# USB_HUB.net
KiCad netlist of a schematic drawn in Altium Designer
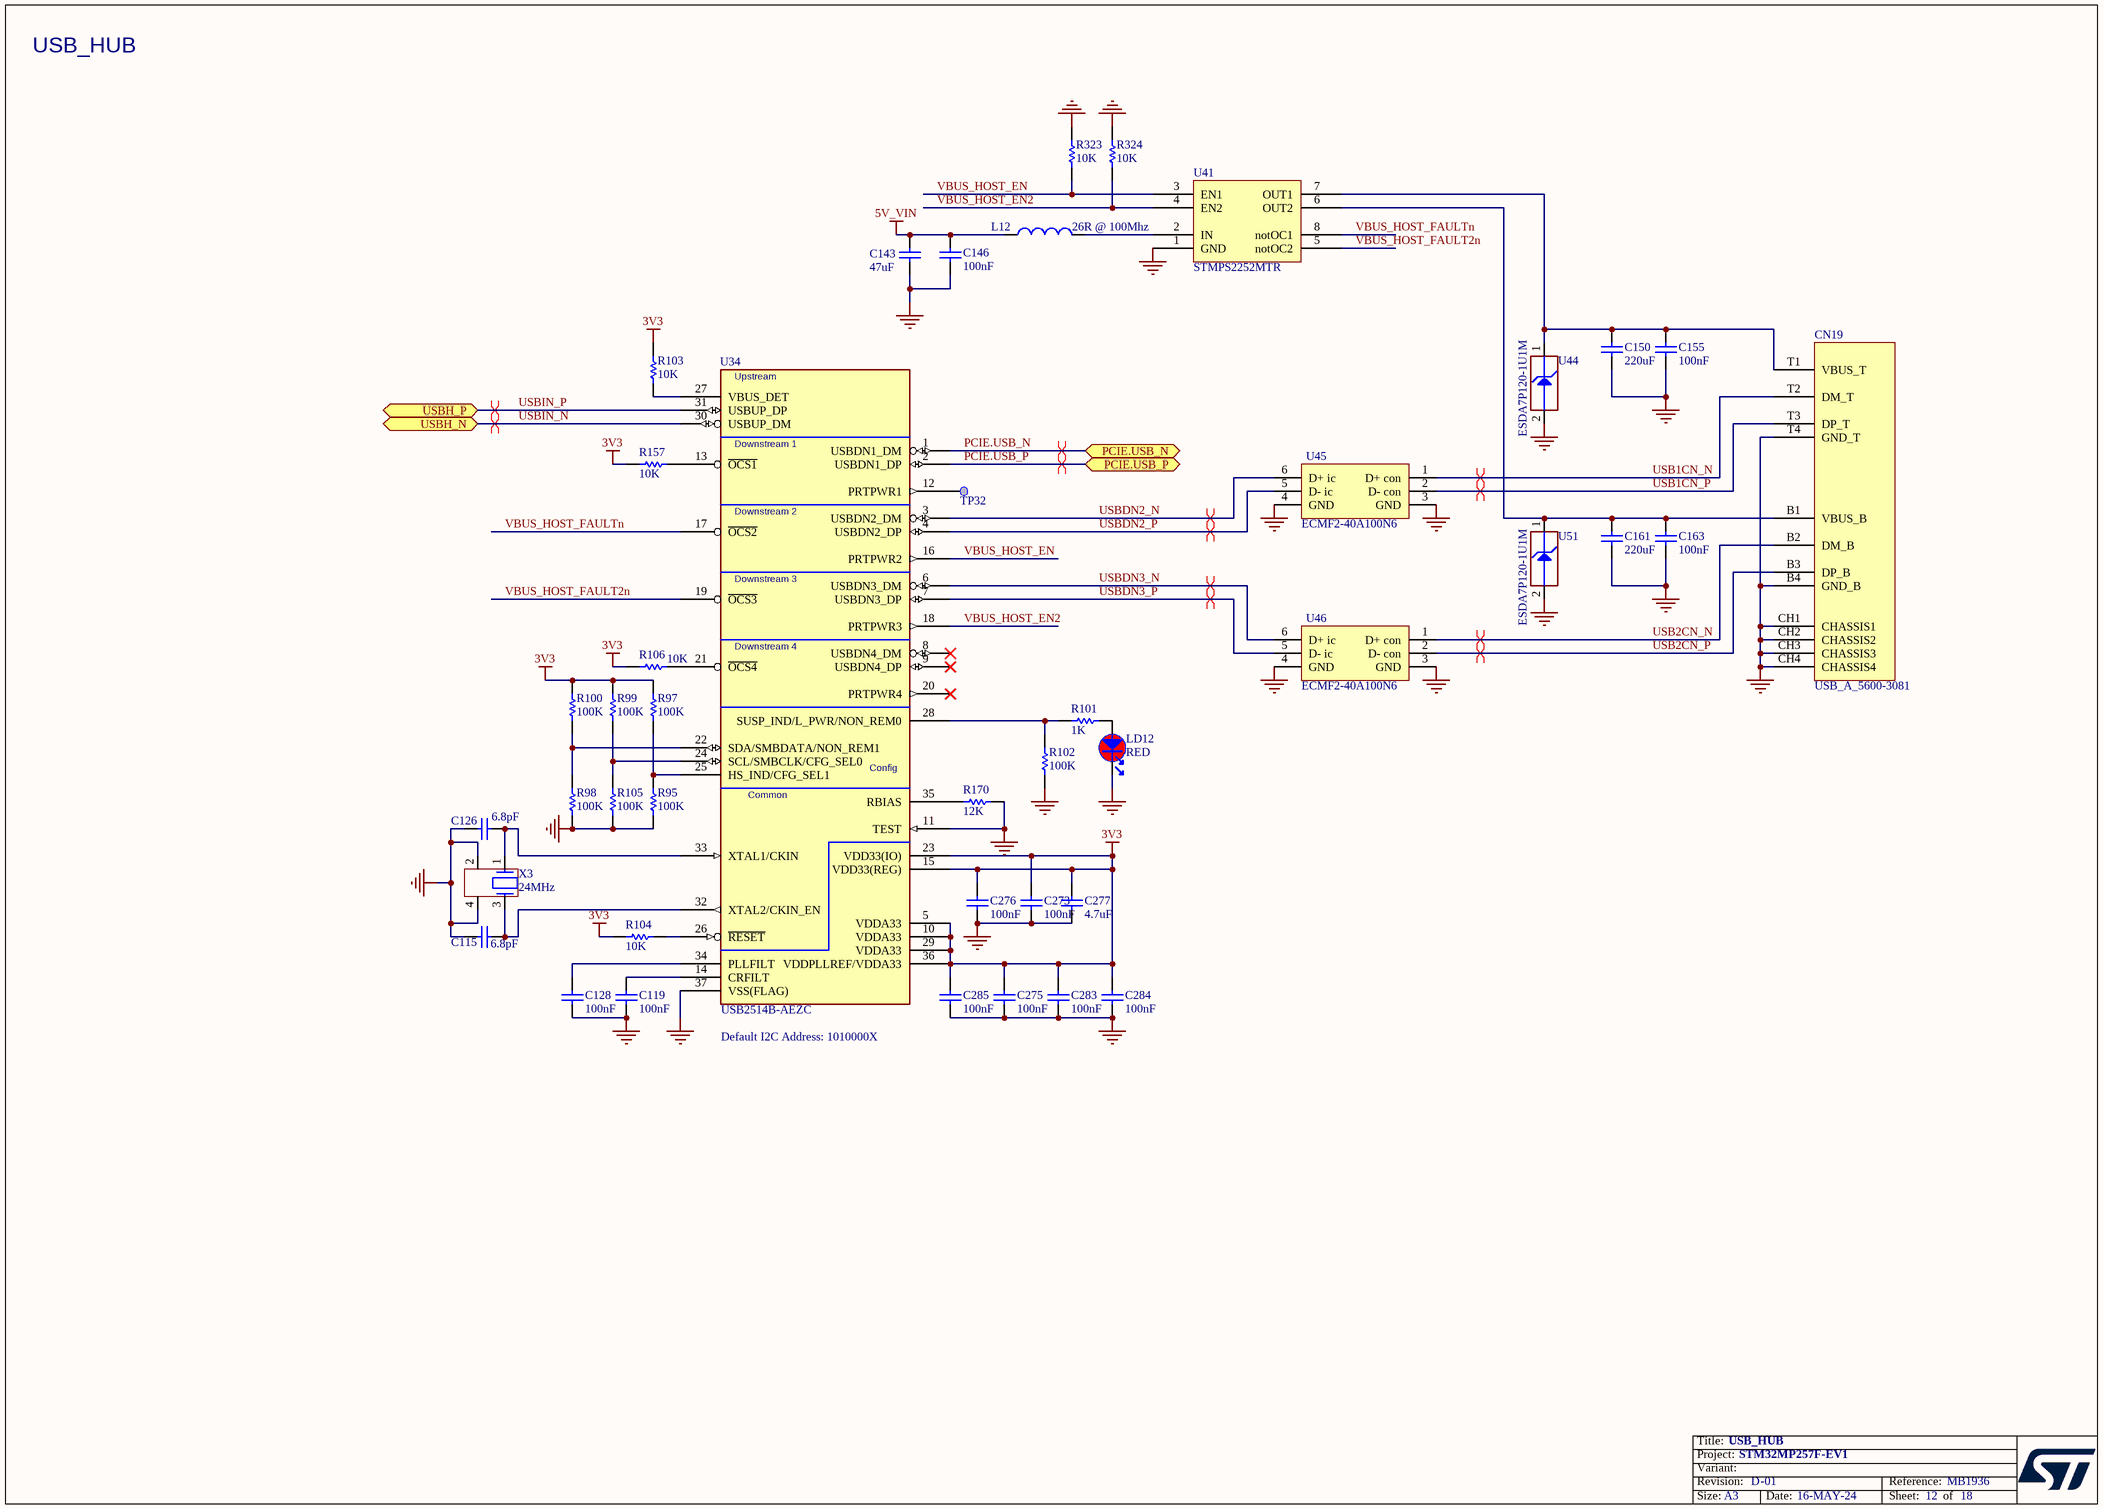
[diagram p0: USB_HUB.SchDoc]

(export (version "E")
  (design (tool "Eeschema 10.0.6"))
  (components
    (comp (ref "C115")
      (value "6.8pF")
      (footprint "MCD_PARTS:C0402")
      (description "Capacitor, MLCC, 6.8pF, 50V, NPO, +/-0.25pF, 0402, T=0.5mm")
      (fields
        (field (name "INTERNAL_PART_NUMBER") "MCD-00674")
        (field (name "MANUFACTURER_PART_NUMBER") "CC0402CRNPO9BN6R8")
      )
      (libsource (lib "MCD_PARTS_database") (part "Capacitor"))
    )
    (comp (ref "C119")
      (value "100nF")
      (footprint "MCD_PARTS:C0402")
      (description "Capacitor, MLCC, 100nF, 16V, X7R, +/-10%, 0402, T=0.5mm")
      (fields
        (field (name "INTERNAL_PART_NUMBER") "MCD-00006")
        (field (name "MANUFACTURER_PART_NUMBER") "CC0402KRX7R7BB104")
      )
      (libsource (lib "MCD_PARTS_database") (part "Capacitor"))
    )
    (comp (ref "C126")
      (value "6.8pF")
      (footprint "MCD_PARTS:C0402")
      (description "Capacitor, MLCC, 6.8pF, 50V, NPO, +/-0.25pF, 0402, T=0.5mm")
      (fields
        (field (name "INTERNAL_PART_NUMBER") "MCD-00674")
        (field (name "MANUFACTURER_PART_NUMBER") "CC0402CRNPO9BN6R8")
      )
      (libsource (lib "MCD_PARTS_database") (part "Capacitor"))
    )
    (comp (ref "C128")
      (value "100nF")
      (footprint "MCD_PARTS:C0402")
      (description "Capacitor, MLCC, 100nF, 16V, X7R, +/-10%, 0402, T=0.5mm")
      (fields
        (field (name "INTERNAL_PART_NUMBER") "MCD-00006")
        (field (name "MANUFACTURER_PART_NUMBER") "CC0402KRX7R7BB104")
      )
      (libsource (lib "MCD_PARTS_database") (part "Capacitor"))
    )
    (comp (ref "C143")
      (value "47uF")
      (footprint "MCD_PARTS:C0805")
      (description "Capacitor, MLCC, 47uF, 10V, X5R, +/-20%, 0805, T=1.25mm")
      (fields (field (name "INTERNAL_PART_NUMBER") "MCD-00204") (field (name "MANUFACTURER") "MURATA"))
      (libsource (lib "MCD_PARTS_database") (part "Capacitor"))
    )
    (comp (ref "C146")
      (value "100nF")
      (footprint "MCD_PARTS:C0402")
      (description "Capacitor, MLCC, 100nF, 16V, X7R, +/-10%, 0402, T=0.5mm")
      (fields
        (field (name "INTERNAL_PART_NUMBER") "MCD-00006")
        (field (name "MANUFACTURER_PART_NUMBER") "CC0402KRX7R7BB104")
      )
      (libsource (lib "MCD_PARTS_database") (part "Capacitor"))
    )
    (comp (ref "C150")
      (value "220uF")
      (footprint "MCD_PARTS:C1206_H1P6")
      (description "Capacitor, MLCC, 220uF, 6V3, X5R, +/-20%, 1206, T=1.6mm")
      (fields
        (field (name "INTERNAL_PART_NUMBER") "MCD-00104")
        (field (name "MANUFACTURER_PART_NUMBER") "GRM31CR60J227ME11")
      )
      (libsource (lib "MCD_PARTS_database") (part "Capacitor"))
    )
    (comp (ref "C155")
      (value "100nF")
      (footprint "MCD_PARTS:C0402")
      (description "Capacitor, MLCC, 100nF, 16V, X7R, +/-10%, 0402, T=0.5mm")
      (fields
        (field (name "INTERNAL_PART_NUMBER") "MCD-00006")
        (field (name "MANUFACTURER_PART_NUMBER") "CC0402KRX7R7BB104")
      )
      (libsource (lib "MCD_PARTS_database") (part "Capacitor"))
    )
    (comp (ref "C161")
      (value "220uF")
      (footprint "MCD_PARTS:C1206_H1P6")
      (description "Capacitor, MLCC, 220uF, 6V3, X5R, +/-20%, 1206, T=1.6mm")
      (fields
        (field (name "INTERNAL_PART_NUMBER") "MCD-00104")
        (field (name "MANUFACTURER_PART_NUMBER") "GRM31CR60J227ME11")
      )
      (libsource (lib "MCD_PARTS_database") (part "Capacitor"))
    )
    (comp (ref "C163")
      (value "100nF")
      (footprint "MCD_PARTS:C0402")
      (description "Capacitor, MLCC, 100nF, 16V, X7R, +/-10%, 0402, T=0.5mm")
      (fields
        (field (name "INTERNAL_PART_NUMBER") "MCD-00006")
        (field (name "MANUFACTURER_PART_NUMBER") "CC0402KRX7R7BB104")
      )
      (libsource (lib "MCD_PARTS_database") (part "Capacitor"))
    )
    (comp (ref "C273")
      (value "100nF")
      (footprint "MCD_PARTS:C0402")
      (description "Capacitor, MLCC, 100nF, 16V, X7R, +/-10%, 0402, T=0.5mm")
      (fields
        (field (name "INTERNAL_PART_NUMBER") "MCD-00006")
        (field (name "MANUFACTURER_PART_NUMBER") "CC0402KRX7R7BB104")
      )
      (libsource (lib "MCD_PARTS_database") (part "Capacitor"))
    )
    (comp (ref "C275")
      (value "100nF")
      (footprint "MCD_PARTS:C0402")
      (description "Capacitor, MLCC, 100nF, 16V, X7R, +/-10%, 0402, T=0.5mm")
      (fields
        (field (name "INTERNAL_PART_NUMBER") "MCD-00006")
        (field (name "MANUFACTURER_PART_NUMBER") "CC0402KRX7R7BB104")
      )
      (libsource (lib "MCD_PARTS_database") (part "Capacitor"))
    )
    (comp (ref "C276")
      (value "100nF")
      (footprint "MCD_PARTS:C0402")
      (description "Capacitor, MLCC, 100nF, 16V, X7R, +/-10%, 0402, T=0.5mm")
      (fields
        (field (name "INTERNAL_PART_NUMBER") "MCD-00006")
        (field (name "MANUFACTURER_PART_NUMBER") "CC0402KRX7R7BB104")
      )
      (libsource (lib "MCD_PARTS_database") (part "Capacitor"))
    )
    (comp (ref "C277")
      (value "4.7uF")
      (footprint "MCD_PARTS:C0402")
      (description "Capacitor, MLCC, 4.7uF, 6V3, X5R, +/-20%, 0402, T=0.5mm")
      (fields
        (field (name "INTERNAL_PART_NUMBER") "MCD-01356")
        (field (name "MANUFACTURER_PART_NUMBER") "GRM155R60J475ME47")
      )
      (libsource (lib "MCD_PARTS_database") (part "Capacitor"))
    )
    (comp (ref "C283")
      (value "100nF")
      (footprint "MCD_PARTS:C0402")
      (description "Capacitor, MLCC, 100nF, 16V, X7R, +/-10%, 0402, T=0.5mm")
      (fields
        (field (name "INTERNAL_PART_NUMBER") "MCD-00006")
        (field (name "MANUFACTURER_PART_NUMBER") "CC0402KRX7R7BB104")
      )
      (libsource (lib "MCD_PARTS_database") (part "Capacitor"))
    )
    (comp (ref "C284")
      (value "100nF")
      (footprint "MCD_PARTS:C0402")
      (description "Capacitor, MLCC, 100nF, 16V, X7R, +/-10%, 0402, T=0.5mm")
      (fields
        (field (name "INTERNAL_PART_NUMBER") "MCD-00006")
        (field (name "MANUFACTURER_PART_NUMBER") "CC0402KRX7R7BB104")
      )
      (libsource (lib "MCD_PARTS_database") (part "Capacitor"))
    )
    (comp (ref "C285")
      (value "100nF")
      (footprint "MCD_PARTS:C0402")
      (description "Capacitor, MLCC, 100nF, 16V, X7R, +/-10%, 0402, T=0.5mm")
      (fields
        (field (name "INTERNAL_PART_NUMBER") "MCD-00006")
        (field (name "MANUFACTURER_PART_NUMBER") "CC0402KRX7R7BB104")
      )
      (libsource (lib "MCD_PARTS_database") (part "Capacitor"))
    )
    (comp (ref "CN19")
      (value "USB_A_5600-3081")
      (footprint "MCD_PARTS:CON_DUAL-USB-TYPE-A_CONEXCON_5600-3081")
      (description "USB_Dual-TypeA, Receptacle, 8pins, 2.5mm, RA, TH, T= 15.5mm")
      (fields
        (field (name "INTERNAL_PART_NUMBER") "MCD-00109")
        (field (name "MANUFACTURER_PART_NUMBER") "5600-3081")
      )
      (libsource (lib "MCD_PARTS_database") (part "USB_DUAL_TYPEA_5600-3081"))
    )
    (comp (ref "L12")
      (value "26R @ 100Mhz")
      (footprint "MCD_PARTS:FIL_0603_H0P65")
      (description "Ferrite bead, 26R @ 100Mhz, +/-25%, 6000mA, 0R007, 0603, T=0.75mm")
      (fields
        (field (name "INTERNAL_PART_NUMBER") "MCD-00305")
        (field (name "MANUFACTURER_PART_NUMBER") "BLM18KG260TN1")
      )
      (libsource (lib "MCD_PARTS_database") (part "BEAD"))
    )
    (comp (ref "LD12")
      (value "RED")
      (footprint "MCD_PARTS:LED_0603_VISHAY_VLMS1300-GS08_RED_1A2K_H0P8")
      (description "LED Red, 0603 SMD, 2V Forward Voltage")
      (fields
        (field (name "INTERNAL_PART_NUMBER") "MCD-00587")
        (field (name "MANUFACTURER_PART_NUMBER") "VLMS1300-GS08")
        (field (name "PROVIDED_BY") "SUBCO")
      )
      (libsource (lib "MCD_PARTS_database") (part "LED_red"))
    )
    (comp (ref "R95")
      (value "100K")
      (footprint "MCD_PARTS:R0402")
      (description "Resistor, 100K, 0402, +/-1%, 1/16W")
      (fields
        (field (name "INTERNAL_PART_NUMBER") "MCD-00059")
        (field (name "MANUFACTURER_PART_NUMBER") "RC0402FR-07100KL")
      )
      (libsource (lib "MCD_PARTS_database") (part "Resistor"))
    )
    (comp (ref "R97")
      (value "100K")
      (footprint "MCD_PARTS:R0402")
      (description "Resistor, 100K, 0402, +/-1%, 1/16W")
      (fields
        (field (name "INTERNAL_PART_NUMBER") "MCD-00059")
        (field (name "MANUFACTURER_PART_NUMBER") "RC0402FR-07100KL")
      )
      (libsource (lib "MCD_PARTS_database") (part "Resistor"))
    )
    (comp (ref "R98")
      (value "100K")
      (footprint "MCD_PARTS:R0402")
      (description "Resistor, 100K, 0402, +/-1%, 1/16W")
      (fields
        (field (name "INTERNAL_PART_NUMBER") "MCD-00059")
        (field (name "MANUFACTURER_PART_NUMBER") "RC0402FR-07100KL")
      )
      (libsource (lib "MCD_PARTS_database") (part "Resistor"))
    )
    (comp (ref "R99")
      (value "100K")
      (footprint "MCD_PARTS:R0402")
      (description "Resistor, 100K, 0402, +/-1%, 1/16W")
      (fields
        (field (name "INTERNAL_PART_NUMBER") "MCD-00059")
        (field (name "MANUFACTURER_PART_NUMBER") "RC0402FR-07100KL")
      )
      (libsource (lib "MCD_PARTS_database") (part "Resistor"))
    )
    (comp (ref "R100")
      (value "100K")
      (footprint "MCD_PARTS:R0402")
      (description "Resistor, 100K, 0402, +/-1%, 1/16W")
      (fields
        (field (name "INTERNAL_PART_NUMBER") "MCD-00059")
        (field (name "MANUFACTURER_PART_NUMBER") "RC0402FR-07100KL")
      )
      (libsource (lib "MCD_PARTS_database") (part "Resistor"))
    )
    (comp (ref "R101")
      (value "1K")
      (footprint "MCD_PARTS:R0402")
      (description "Resistor, 1K, 0402, +/-1%,1/16W")
      (fields
        (field (name "INTERNAL_PART_NUMBER") "MCD-00061")
        (field (name "MANUFACTURER_PART_NUMBER") "RC0402FR-071KL")
      )
      (libsource (lib "MCD_PARTS_database") (part "Resistor"))
    )
    (comp (ref "R102")
      (value "100K")
      (footprint "MCD_PARTS:R0402")
      (description "Resistor, 100K, 0402, +/-1%, 1/16W")
      (fields
        (field (name "INTERNAL_PART_NUMBER") "MCD-00059")
        (field (name "MANUFACTURER_PART_NUMBER") "RC0402FR-07100KL")
      )
      (libsource (lib "MCD_PARTS_database") (part "Resistor"))
    )
    (comp (ref "R103")
      (value "10K")
      (footprint "MCD_PARTS:R0402")
      (description "Resistor, 10K, 0402, +/-1%, 1/16W")
      (fields
        (field (name "INTERNAL_PART_NUMBER") "MCD-00053")
        (field (name "MANUFACTURER_PART_NUMBER") "RC0402FR-0710KL")
      )
      (libsource (lib "MCD_PARTS_database") (part "Resistor"))
    )
    (comp (ref "R104")
      (value "10K")
      (footprint "MCD_PARTS:R0402")
      (description "Resistor, 10K, 0402, +/-1%, 1/16W")
      (fields
        (field (name "INTERNAL_PART_NUMBER") "MCD-00053")
        (field (name "MANUFACTURER_PART_NUMBER") "RC0402FR-0710KL")
      )
      (libsource (lib "MCD_PARTS_database") (part "Resistor"))
    )
    (comp (ref "R105")
      (value "100K")
      (footprint "MCD_PARTS:R0402")
      (description "Resistor, 100K, 0402, +/-1%, 1/16W")
      (fields
        (field (name "INTERNAL_PART_NUMBER") "MCD-00059")
        (field (name "MANUFACTURER_PART_NUMBER") "RC0402FR-07100KL")
      )
      (libsource (lib "MCD_PARTS_database") (part "Resistor"))
    )
    (comp (ref "R106")
      (value "10K")
      (footprint "MCD_PARTS:R0402")
      (description "Resistor, 10K, 0402, +/-1%, 1/16W")
      (fields
        (field (name "INTERNAL_PART_NUMBER") "MCD-00053")
        (field (name "MANUFACTURER_PART_NUMBER") "RC0402FR-0710KL")
      )
      (libsource (lib "MCD_PARTS_database") (part "Resistor"))
    )
    (comp (ref "R157")
      (value "10K")
      (footprint "MCD_PARTS:R0402")
      (description "Resistor, 10K, 0402, +/-1%, 1/16W")
      (fields
        (field (name "INTERNAL_PART_NUMBER") "MCD-00053")
        (field (name "MANUFACTURER_PART_NUMBER") "RC0402FR-0710KL")
      )
      (libsource (lib "MCD_PARTS_database") (part "Resistor"))
    )
    (comp (ref "R170")
      (value "12K")
      (footprint "MCD_PARTS:R0402")
      (description "Resistor, 12K, 0402, +/-1%, 1/16W")
      (fields
        (field (name "INTERNAL_PART_NUMBER") "MCD-00187")
        (field (name "MANUFACTURER_PART_NUMBER") "RC0402FR-0712KL")
      )
      (libsource (lib "MCD_PARTS_database") (part "Resistor"))
    )
    (comp (ref "R323")
      (value "10K")
      (footprint "MCD_PARTS:R0402")
      (description "Resistor, 10K, 0402, +/-1%, 1/16W")
      (fields
        (field (name "INTERNAL_PART_NUMBER") "MCD-00053")
        (field (name "MANUFACTURER_PART_NUMBER") "RC0402FR-0710KL")
      )
      (libsource (lib "MCD_PARTS_database") (part "Resistor"))
    )
    (comp (ref "R324")
      (value "10K")
      (footprint "MCD_PARTS:R0402")
      (description "Resistor, 10K, 0402, +/-1%, 1/16W")
      (fields
        (field (name "INTERNAL_PART_NUMBER") "MCD-00053")
        (field (name "MANUFACTURER_PART_NUMBER") "RC0402FR-0710KL")
      )
      (libsource (lib "MCD_PARTS_database") (part "Resistor"))
    )
    (comp (ref "TP32")
      (value "Test Point")
      (footprint "MCD_PARTS:TP_SMD_1MM")
      (description "Test Point 1mm")
      (fields
        (field (name "INTERNAL_PART_NUMBER") "MCD-00074")
        (field (name "MANUFACTURER_PART_NUMBER") "n/a")
      )
      (libsource (lib "MCD_PARTS_database") (part "Test Point"))
    )
    (comp (ref "U34")
      (value "USB2514B-AEZC")
      (footprint "MCD_PARTS:ICC_QFN36-EPAD_6X6_P050")
      (description "USB HUB 2,0 Controller")
      (fields (field (name "INTERNAL_PART_NUMBER") "MCD-00145") (field (name "MANUFACTURER") "MICROCHIP"))
      (libsource (lib "MCD_PARTS_database") (part "USB2514B-AEZC"))
    )
    (comp (ref "U41")
      (value "STMPS2252MTR")
      (footprint "MCD_PARTS:ICC_SO8_5X4_P127")
      (description "IC,Dual-Channel-Power-Switch,500mA,100mR,SO8")
      (fields
        (field (name "INTERNAL_PART_NUMBER") "MCD-00123")
        (field (name "MANUFACTURER") "STMICROELECTRONICS")
      )
      (libsource (lib "MCD_PARTS_database") (part "STMPS2252MTR"))
    )
    (comp (ref "U44")
      (value "ESDA7P120-1U1M")
      (footprint "MCD_PARTS:ESD_QFN1610_2N_1K_2A")
      (description "High power transient voltage suppressor")
      (fields
        (field (name "INTERNAL_PART_NUMBER") "MCD-01026")
        (field (name "MANUFACTURER") "STMICROELECTRONICS")
      )
      (libsource (lib "MCD_PARTS_database") (part "ESD-TRANSIL"))
    )
    (comp (ref "U45")
      (value "ECMF2-40A100N6")
      (footprint "MCD_PARTS:ESD_UQFN-6L_1P45X1P4_P040")
      (description "ESD protection & Common Filter High Speed serial Interfaces , 0.4 pitch")
      (fields
        (field (name "INTERNAL_PART_NUMBER") "MCD-03060")
        (field (name "MANUFACTURER") "STMICROELECTRONICS")
      )
      (libsource (lib "MCD_PARTS_database") (part "ECMF2-40A100N6"))
    )
    (comp (ref "U46")
      (value "ECMF2-40A100N6")
      (footprint "MCD_PARTS:ESD_UQFN-6L_1P45X1P4_P040")
      (description "ESD protection & Common Filter High Speed serial Interfaces , 0.4 pitch")
      (fields
        (field (name "INTERNAL_PART_NUMBER") "MCD-03060")
        (field (name "MANUFACTURER") "STMICROELECTRONICS")
      )
      (libsource (lib "MCD_PARTS_database") (part "ECMF2-40A100N6"))
    )
    (comp (ref "U51")
      (value "ESDA7P120-1U1M")
      (footprint "MCD_PARTS:ESD_QFN1610_2N_1K_2A")
      (description "High power transient voltage suppressor")
      (fields
        (field (name "INTERNAL_PART_NUMBER") "MCD-01026")
        (field (name "MANUFACTURER") "STMICROELECTRONICS")
      )
      (libsource (lib "MCD_PARTS_database") (part "ESD-TRANSIL"))
    )
    (comp (ref "X3")
      (value "24MHz")
      (footprint "MCD_PARTS:CRY_NX2016SA_4P")
      (description "Crystal, 24MHz, 6pF, +/-20ppm, 80R, 2x1.6mm")
      (fields
        (field (name "INTERNAL_PART_NUMBER") "MCD-01036")
        (field (name "MANUFACTURER_PART_NUMBER") "NX2016SA-24MHZ-EXS00A-CS10820")
      )
      (libsource (lib "MCD_PARTS_database") (part "XTAL_4_PINS"))
    )
  )
  (nets
    (net (code "1") (name "/PCIE.USB_N") (class "Default")
      (node (ref "U34") (pin "1") (pinfunction "USBDN1_DM_1") (pintype "bidirectional"))
    )
    (net (code "2") (name "/PCIE.USB_P") (class "Default")
      (node (ref "U34") (pin "2") (pinfunction "USBDN1_DP_2") (pintype "bidirectional"))
    )
    (net (code "3") (name "/USB1CN_N") (class "Default")
      (node (ref "CN19") (pin "T2") (pinfunction "DM_T_T2") (pintype "passive"))
      (node (ref "U45") (pin "1") (pinfunction "D+_con_1") (pintype "passive"))
    )
    (net (code "4") (name "/USB1CN_P") (class "Default")
      (node (ref "CN19") (pin "T3") (pinfunction "DP_T_T3") (pintype "passive"))
      (node (ref "U45") (pin "2") (pinfunction "D-_con_2") (pintype "passive"))
    )
    (net (code "5") (name "/USB2CN_N") (class "Default")
      (node (ref "CN19") (pin "B2") (pinfunction "DM_B_B2") (pintype "passive"))
      (node (ref "U46") (pin "1") (pinfunction "D+_con_1") (pintype "passive"))
    )
    (net (code "6") (name "/USB2CN_P") (class "Default")
      (node (ref "CN19") (pin "B3") (pinfunction "DP_B_B3") (pintype "passive"))
      (node (ref "U46") (pin "2") (pinfunction "D-_con_2") (pintype "passive"))
    )
    (net (code "7") (name "/USBDN2_N") (class "Default")
      (node (ref "U34") (pin "3") (pinfunction "USBDN2_DM_3") (pintype "bidirectional"))
      (node (ref "U45") (pin "6") (pinfunction "D+_ic_6") (pintype "passive"))
    )
    (net (code "8") (name "/USBDN2_P") (class "Default")
      (node (ref "U34") (pin "4") (pinfunction "USBDN2_DP_4") (pintype "bidirectional"))
      (node (ref "U45") (pin "5") (pinfunction "D-_ic_5") (pintype "passive"))
    )
    (net (code "9") (name "/USBDN3_N") (class "Default")
      (node (ref "U34") (pin "6") (pinfunction "USBDN3_DM_6") (pintype "bidirectional"))
      (node (ref "U46") (pin "6") (pinfunction "D+_ic_6") (pintype "passive"))
    )
    (net (code "10") (name "/USBDN3_P") (class "Default")
      (node (ref "U34") (pin "7") (pinfunction "USBDN3_DP_7") (pintype "bidirectional"))
      (node (ref "U46") (pin "5") (pinfunction "D-_ic_5") (pintype "passive"))
    )
    (net (code "11") (name "/USBIN_N") (class "Default")
      (node (ref "U34") (pin "30") (pinfunction "USBUP_DM_30") (pintype "bidirectional"))
    )
    (net (code "12") (name "/USBIN_P") (class "Default")
      (node (ref "U34") (pin "31") (pinfunction "USBUP_DP_31") (pintype "bidirectional"))
    )
    (net (code "13") (name "/VBUS_HOST_EN") (class "Default")
      (node (ref "R323") (pin "2") (pinfunction "2_2") (pintype "passive"))
      (node (ref "U34") (pin "16") (pinfunction "PRTPWR2_16") (pintype "output"))
      (node (ref "U41") (pin "3") (pinfunction "EN1_3") (pintype "passive"))
    )
    (net (code "14") (name "/VBUS_HOST_EN2") (class "Default")
      (node (ref "R324") (pin "2") (pinfunction "2_2") (pintype "passive"))
      (node (ref "U34") (pin "18") (pinfunction "PRTPWR3_18") (pintype "output"))
      (node (ref "U41") (pin "4") (pinfunction "EN2_4") (pintype "passive"))
    )
    (net (code "15") (name "/VBUS_HOST_FAULT2n") (class "Default")
      (node (ref "U34") (pin "19") (pinfunction "~{OCS3}_19") (pintype "passive"))
      (node (ref "U41") (pin "5") (pinfunction "notOC2_5") (pintype "passive"))
    )
    (net (code "16") (name "/VBUS_HOST_FAULTn") (class "Default")
      (node (ref "U34") (pin "17") (pinfunction "~{OCS2}_17") (pintype "passive"))
      (node (ref "U41") (pin "8") (pinfunction "notOC1_8") (pintype "passive"))
    )
    (net (code "17") (name "3V3") (class "Default")
      (node (ref "C273") (pin "2") (pinfunction "2_2") (pintype "passive"))
      (node (ref "C275") (pin "2") (pinfunction "2_2") (pintype "passive"))
      (node (ref "C276") (pin "2") (pinfunction "2_2") (pintype "passive"))
      (node (ref "C277") (pin "2") (pinfunction "2_2") (pintype "passive"))
      (node (ref "C283") (pin "2") (pinfunction "2_2") (pintype "passive"))
      (node (ref "C284") (pin "2") (pinfunction "2_2") (pintype "passive"))
      (node (ref "C285") (pin "2") (pinfunction "2_2") (pintype "passive"))
      (node (ref "R100") (pin "2") (pinfunction "2_2") (pintype "passive"))
      (node (ref "R103") (pin "2") (pinfunction "2_2") (pintype "passive"))
      (node (ref "R104") (pin "1") (pinfunction "1_1") (pintype "passive"))
      (node (ref "R106") (pin "2") (pinfunction "2_2") (pintype "passive"))
      (node (ref "R157") (pin "2") (pinfunction "2_2") (pintype "passive"))
      (node (ref "R97") (pin "2") (pinfunction "2_2") (pintype "passive"))
      (node (ref "R99") (pin "2") (pinfunction "2_2") (pintype "passive"))
      (node (ref "U34") (pin "10") (pinfunction "VDDA33_10") (pintype "power_in"))
      (node (ref "U34") (pin "15") (pinfunction "VDD33(REG)_15") (pintype "power_in"))
      (node (ref "U34") (pin "23") (pinfunction "VDD33(IO)_23") (pintype "power_in"))
      (node (ref "U34") (pin "29") (pinfunction "VDDA33_29") (pintype "power_in"))
      (node (ref "U34") (pin "36") (pinfunction "VDDPLLREF/VDDA33_36") (pintype "power_in"))
      (node (ref "U34") (pin "5") (pinfunction "VDDA33_5") (pintype "power_in"))
    )
    (net (code "18") (name "5V_VIN") (class "Default")
      (node (ref "C143") (pin "2") (pinfunction "2_2") (pintype "passive"))
      (node (ref "C146") (pin "2") (pinfunction "2_2") (pintype "passive"))
      (node (ref "L12") (pin "1") (pinfunction "1_1") (pintype "passive"))
    )
    (net (code "19") (name "GND") (class "Default")
      (node (ref "C115") (pin "1") (pinfunction "1_1") (pintype "passive"))
      (node (ref "C119") (pin "1") (pinfunction "1_1") (pintype "passive"))
      (node (ref "C126") (pin "1") (pinfunction "1_1") (pintype "passive"))
      (node (ref "C128") (pin "1") (pinfunction "1_1") (pintype "passive"))
      (node (ref "C143") (pin "1") (pinfunction "1_1") (pintype "passive"))
      (node (ref "C146") (pin "1") (pinfunction "1_1") (pintype "passive"))
      (node (ref "C150") (pin "1") (pinfunction "1_1") (pintype "passive"))
      (node (ref "C155") (pin "1") (pinfunction "1_1") (pintype "passive"))
      (node (ref "C161") (pin "1") (pinfunction "1_1") (pintype "passive"))
      (node (ref "C163") (pin "1") (pinfunction "1_1") (pintype "passive"))
      (node (ref "C273") (pin "1") (pinfunction "1_1") (pintype "passive"))
      (node (ref "C275") (pin "1") (pinfunction "1_1") (pintype "passive"))
      (node (ref "C276") (pin "1") (pinfunction "1_1") (pintype "passive"))
      (node (ref "C277") (pin "1") (pinfunction "1_1") (pintype "passive"))
      (node (ref "C283") (pin "1") (pinfunction "1_1") (pintype "passive"))
      (node (ref "C284") (pin "1") (pinfunction "1_1") (pintype "passive"))
      (node (ref "C285") (pin "1") (pinfunction "1_1") (pintype "passive"))
      (node (ref "CN19") (pin "B4") (pinfunction "GND_B_B4") (pintype "passive"))
      (node (ref "CN19") (pin "CH1") (pinfunction "CHASSIS1_CH1") (pintype "passive"))
      (node (ref "CN19") (pin "CH2") (pinfunction "CHASSIS2_CH2") (pintype "passive"))
      (node (ref "CN19") (pin "CH3") (pinfunction "CHASSIS3_CH3") (pintype "passive"))
      (node (ref "CN19") (pin "CH4") (pinfunction "CHASSIS4_CH4") (pintype "passive"))
      (node (ref "CN19") (pin "T4") (pinfunction "GND_T_T4") (pintype "passive"))
      (node (ref "LD12") (pin "2") (pintype "passive"))
      (node (ref "R102") (pin "1") (pinfunction "1_1") (pintype "passive"))
      (node (ref "R105") (pin "1") (pinfunction "1_1") (pintype "passive"))
      (node (ref "R170") (pin "1") (pinfunction "1_1") (pintype "passive"))
      (node (ref "R323") (pin "1") (pinfunction "1_1") (pintype "passive"))
      (node (ref "R324") (pin "1") (pinfunction "1_1") (pintype "passive"))
      (node (ref "R95") (pin "1") (pinfunction "1_1") (pintype "passive"))
      (node (ref "R98") (pin "1") (pinfunction "1_1") (pintype "passive"))
      (node (ref "U34") (pin "11") (pinfunction "TEST_11") (pintype "input"))
      (node (ref "U34") (pin "37") (pinfunction "VSS(FLAG)_37") (pintype "power_in"))
      (node (ref "U41") (pin "1") (pinfunction "GND_1") (pintype "passive"))
      (node (ref "U44") (pin "2") (pinfunction "GND_2") (pintype "passive"))
      (node (ref "U45") (pin "3") (pinfunction "GND_3") (pintype "passive"))
      (node (ref "U45") (pin "4") (pinfunction "GND_4") (pintype "passive"))
      (node (ref "U46") (pin "3") (pinfunction "GND_3") (pintype "passive"))
      (node (ref "U46") (pin "4") (pinfunction "GND_4") (pintype "passive"))
      (node (ref "U51") (pin "2") (pinfunction "GND_2") (pintype "passive"))
      (node (ref "X3") (pin "2") (pinfunction "2_2") (pintype "passive"))
      (node (ref "X3") (pin "4") (pinfunction "4_4") (pintype "passive"))
    )
    (net (code "20") (name "Net-(CN19-VBUS_B)") (class "Default")
      (node (ref "C161") (pin "2") (pinfunction "2_2") (pintype "passive"))
      (node (ref "C163") (pin "2") (pinfunction "2_2") (pintype "passive"))
      (node (ref "CN19") (pin "B1") (pinfunction "VBUS_B_B1") (pintype "passive"))
      (node (ref "U41") (pin "6") (pinfunction "OUT2_6") (pintype "passive"))
      (node (ref "U51") (pin "1") (pinfunction "IO1_1") (pintype "passive"))
    )
    (net (code "21") (name "Net-(CN19-VBUS_T)") (class "Default")
      (node (ref "C150") (pin "2") (pinfunction "2_2") (pintype "passive"))
      (node (ref "C155") (pin "2") (pinfunction "2_2") (pintype "passive"))
      (node (ref "CN19") (pin "T1") (pinfunction "VBUS_T_T1") (pintype "passive"))
      (node (ref "U41") (pin "7") (pinfunction "OUT1_7") (pintype "passive"))
      (node (ref "U44") (pin "1") (pinfunction "IO1_1") (pintype "passive"))
    )
    (net (code "22") (name "Net-(LD12-Pad1)") (class "Default")
      (node (ref "LD12") (pin "1") (pintype "passive"))
      (node (ref "R101") (pin "1") (pinfunction "1_1") (pintype "passive"))
    )
    (net (code "23") (name "Net-(U34-CRFILT)") (class "Default")
      (node (ref "C119") (pin "2") (pinfunction "2_2") (pintype "passive"))
      (node (ref "U34") (pin "14") (pinfunction "CRFILT_14") (pintype "power_in"))
    )
    (net (code "24") (name "Net-(U34-HS_IND{slash}CFG_SEL1)") (class "Default")
      (node (ref "R95") (pin "2") (pinfunction "2_2") (pintype "passive"))
      (node (ref "R97") (pin "1") (pinfunction "1_1") (pintype "passive"))
      (node (ref "U34") (pin "25") (pinfunction "HS_IND/CFG_SEL1_25") (pintype "passive"))
    )
    (net (code "25") (name "Net-(U34-PLLFILT)") (class "Default")
      (node (ref "C128") (pin "2") (pinfunction "2_2") (pintype "passive"))
      (node (ref "U34") (pin "34") (pinfunction "PLLFILT_34") (pintype "power_in"))
    )
    (net (code "26") (name "Net-(U34-PRTPWR1)") (class "Default")
      (node (ref "TP32") (pin "1") (pinfunction "1_1") (pintype "passive"))
      (node (ref "U34") (pin "12") (pinfunction "PRTPWR1_12") (pintype "output"))
    )
    (net (code "27") (name "Net-(U34-RBIAS)") (class "Default")
      (node (ref "R170") (pin "2") (pinfunction "2_2") (pintype "passive"))
      (node (ref "U34") (pin "35") (pinfunction "RBIAS_35") (pintype "passive"))
    )
    (net (code "28") (name "Net-(U34-SCL{slash}SMBCLK{slash}CFG_SEL0)") (class "Default")
      (node (ref "R105") (pin "2") (pinfunction "2_2") (pintype "passive"))
      (node (ref "R99") (pin "1") (pinfunction "1_1") (pintype "passive"))
      (node (ref "U34") (pin "24") (pinfunction "SCL/SMBCLK/CFG_SEL0_24") (pintype "bidirectional"))
    )
    (net (code "29") (name "Net-(U34-SDA{slash}SMBDATA{slash}NON_REM1)") (class "Default")
      (node (ref "R100") (pin "1") (pinfunction "1_1") (pintype "passive"))
      (node (ref "R98") (pin "2") (pinfunction "2_2") (pintype "passive"))
      (node (ref "U34") (pin "22") (pinfunction "SDA/SMBDATA/NON_REM1_22") (pintype "bidirectional"))
    )
    (net (code "30") (name "Net-(U34-SUSP_IND{slash}L_PWR{slash}NON_REM0)") (class "Default")
      (node (ref "R101") (pin "2") (pinfunction "2_2") (pintype "passive"))
      (node (ref "R102") (pin "2") (pinfunction "2_2") (pintype "passive"))
      (node (ref "U34") (pin "28") (pinfunction "SUSP_IND/L_PWR/NON_REM0_28") (pintype "passive"))
    )
    (net (code "31") (name "Net-(U34-VBUS_DET)") (class "Default")
      (node (ref "R103") (pin "1") (pinfunction "1_1") (pintype "passive"))
      (node (ref "U34") (pin "27") (pinfunction "VBUS_DET_27") (pintype "passive"))
    )
    (net (code "32") (name "Net-(U34-XTAL1{slash}CKIN)") (class "Default")
      (node (ref "C126") (pin "2") (pinfunction "2_2") (pintype "passive"))
      (node (ref "U34") (pin "33") (pinfunction "XTAL1/CKIN_33") (pintype "input"))
      (node (ref "X3") (pin "1") (pinfunction "1_1") (pintype "passive"))
    )
    (net (code "33") (name "Net-(U34-XTAL2{slash}CKIN_EN)") (class "Default")
      (node (ref "C115") (pin "2") (pinfunction "2_2") (pintype "passive"))
      (node (ref "U34") (pin "32") (pinfunction "XTAL2/CKIN_EN_32") (pintype "output"))
      (node (ref "X3") (pin "3") (pinfunction "3_3") (pintype "passive"))
    )
    (net (code "34") (name "Net-(U34-~{OCS1})") (class "Default")
      (node (ref "R157") (pin "1") (pinfunction "1_1") (pintype "passive"))
      (node (ref "U34") (pin "13") (pinfunction "~{OCS1}_13") (pintype "passive"))
    )
    (net (code "35") (name "Net-(U34-~{OCS4})") (class "Default")
      (node (ref "R106") (pin "1") (pinfunction "1_1") (pintype "passive"))
      (node (ref "U34") (pin "21") (pinfunction "~{OCS4}_21") (pintype "passive"))
    )
    (net (code "36") (name "Net-(U34-~{RESET})") (class "Default")
      (node (ref "R104") (pin "2") (pinfunction "2_2") (pintype "passive"))
      (node (ref "U34") (pin "26") (pinfunction "~{RESET}_26") (pintype "input"))
    )
    (net (code "37") (name "Net-(U41-IN)") (class "Default")
      (node (ref "L12") (pin "2") (pinfunction "2_2") (pintype "passive"))
      (node (ref "U41") (pin "2") (pinfunction "IN_2") (pintype "passive"))
    )
    (net (code "38") (name "unconnected-(U34-PRTPWR4-Pad20)") (class "Default")
      (node (ref "U34") (pin "20") (pinfunction "PRTPWR4_20") (pintype "output+no_connect"))
    )
    (net (code "39") (name "unconnected-(U34-USBDN4_DM-Pad8)") (class "Default")
      (node (ref "U34") (pin "8") (pinfunction "USBDN4_DM_8") (pintype "bidirectional+no_connect"))
    )
    (net (code "40") (name "unconnected-(U34-USBDN4_DP-Pad9)") (class "Default")
      (node (ref "U34") (pin "9") (pinfunction "USBDN4_DP_9") (pintype "bidirectional+no_connect"))
    )
  )
)
